# AMS_CAN.net
KiCad netlist of a schematic drawn in Altium Designer
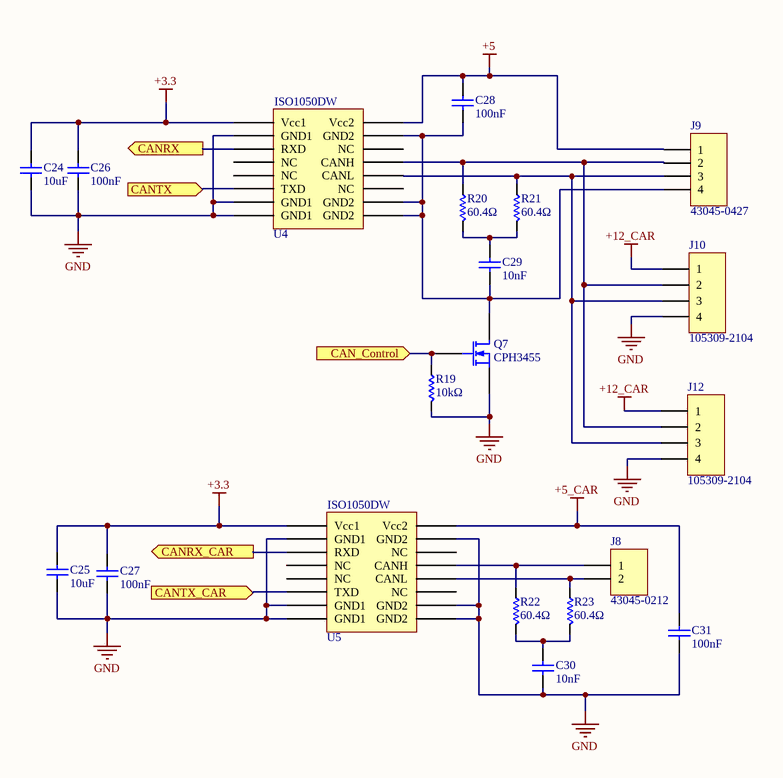
[diagram p0: AMS_CAN.SchDoc]

(export (version "E")
  (design (tool "Eeschema 10.0.6"))
  (components
    (comp (ref "C24")
      (value "10uF")
      (footprint "0805_2x1.25x1.25mm_Reflow Soldering")
      (description "WCAP-CSGP Ceramic Capacitors, 0805, X5R, 16V, 10uF")
      (fields (field (name "PART NUMBER") "885012107014") (field (name "PUBLISHER") "Wurth Elektronik"))
      (libsource (lib "Components_Library") (part "885012107014"))
    )
    (comp (ref "C25")
      (value "10uF")
      (footprint "0805_2x1.25x1.25mm_Reflow Soldering")
      (description "WCAP-CSGP Ceramic Capacitors, 0805, X5R, 16V, 10uF")
      (fields (field (name "PART NUMBER") "885012107014") (field (name "PUBLISHER") "Wurth Elektronik"))
      (libsource (lib "Components_Library") (part "885012107014"))
    )
    (comp (ref "C26")
      (value "100nF")
      (footprint "0805_2x1.25x0.8mm_Reflow Soldering")
      (description "WCAP-CSGP Ceramic Capacitors, 0805, X7R, 50V, 100nF")
      (fields (field (name "PART NUMBER") "885012207098") (field (name "PUBLISHER") "Wurth Elektronik"))
      (libsource (lib "Components_Library") (part "885012207098"))
    )
    (comp (ref "C27")
      (value "100nF")
      (footprint "0805_2x1.25x0.8mm_Reflow Soldering")
      (description "WCAP-CSGP Ceramic Capacitors, 0805, X7R, 50V, 100nF")
      (fields (field (name "PART NUMBER") "885012207098") (field (name "PUBLISHER") "Wurth Elektronik"))
      (libsource (lib "Components_Library") (part "885012207098"))
    )
    (comp (ref "C28")
      (value "100nF")
      (footprint "0805_2x1.25x0.8mm_Reflow Soldering")
      (description "WCAP-CSGP Ceramic Capacitors, 0805, X7R, 50V, 100nF")
      (fields (field (name "PART NUMBER") "885012207098") (field (name "PUBLISHER") "Wurth Elektronik"))
      (libsource (lib "Components_Library") (part "885012207098"))
    )
    (comp (ref "C29")
      (value "10nF")
      (footprint "0805_2x1.25x0.8mm_Reflow Soldering")
      (description "WCAP-CSGP Ceramic Capacitors, 0805, X7R, 50V, 10nF")
      (fields (field (name "PART NUMBER") "885012207092") (field (name "PUBLISHER") "Wurth Elektronik"))
      (libsource (lib "Components_Library") (part "885012207092"))
    )
    (comp (ref "C30")
      (value "10nF")
      (footprint "0805_2x1.25x0.8mm_Reflow Soldering")
      (description "WCAP-CSGP Ceramic Capacitors, 0805, X7R, 50V, 10nF")
      (fields (field (name "PART NUMBER") "885012207092") (field (name "PUBLISHER") "Wurth Elektronik"))
      (libsource (lib "Components_Library") (part "885012207092"))
    )
    (comp (ref "C31")
      (value "100nF")
      (footprint "0805_2x1.25x0.8mm_Reflow Soldering")
      (description "WCAP-CSGP Ceramic Capacitors, 0805, X7R, 50V, 100nF")
      (fields (field (name "PART NUMBER") "885012207098") (field (name "PUBLISHER") "Wurth Elektronik"))
      (libsource (lib "Components_Library") (part "885012207098"))
    )
    (comp (ref "J8")
      (value "43045-0212")
      (footprint "43045-0212")
      (description "Micro-Fit 3.0 Vertical Header, 3.00mm Pitch, Dual Row, 2 Circuits, Black")
      (fields (field (name "MANUFACTURER") "Molex"))
      (libsource (lib "Components_Library") (part "43045-0212"))
    )
    (comp (ref "J9")
      (value "43045-0427")
      (footprint "43045-0427")
      (description "Micro-Fit 3.0 Vertical Header, 3.00mm Pitch, Dual Row, 4 Circuits, Black")
      (fields (field (name "MANUFACTURER") "Molex"))
      (libsource (lib "Components_Library") (part "43045-0427"))
    )
    (comp (ref "J10")
      (value "105309-2104")
      (footprint "105309-2104")
      (description "Nano-Fit Vertical Header, Through Hole, 2.50mm Pitch, Single Row, 4 Circuits, Natural")
      (fields (field (name "MANUFACTURER") "Molex"))
      (libsource (lib "Components_Library") (part "105309-2104"))
    )
    (comp (ref "J12")
      (value "105309-2104")
      (footprint "105309-2104")
      (description "Nano-Fit Vertical Header, Through Hole, 2.50mm Pitch, Single Row, 4 Circuits, Natural")
      (fields (field (name "MANUFACTURER") "Molex"))
      (libsource (lib "Components_Library") (part "105309-2104"))
    )
    (comp (ref "Q7")
      (value "CPH3455")
      (footprint "CPH3455")
      (description "Power MOSFET 35V, 104mΩ, 3A, Single N-Channel")
      (fields (field (name "MANUFACTURER") "ON Semiconductors"))
      (libsource (lib "Components_Library") (part "CPH3455"))
    )
    (comp (ref "R19")
      (value "10kΩ")
      (footprint "CR0805")
      (description "Chip Resistor 0805")
      (fields (field (name "MANUFACTURER") "Bourns"))
      (libsource (lib "Components_Library") (part "CR0805-JW-103ELF"))
    )
    (comp (ref "R20")
      (value "60.4Ω")
      (footprint "CR0805")
      (description "Chip Resistor 0805")
      (fields (field (name "MANUFACTURER") "Panasonic"))
      (libsource (lib "Components_Library") (part "ERA6AEB60R4V"))
    )
    (comp (ref "R21")
      (value "60.4Ω")
      (footprint "CR0805")
      (description "Chip Resistor 0805")
      (fields (field (name "MANUFACTURER") "Panasonic"))
      (libsource (lib "Components_Library") (part "ERA6AEB60R4V"))
    )
    (comp (ref "R22")
      (value "60.4Ω")
      (footprint "CR0805")
      (description "Chip Resistor 0805")
      (fields (field (name "MANUFACTURER") "Panasonic"))
      (libsource (lib "Components_Library") (part "ERA6AEB60R4V"))
    )
    (comp (ref "R23")
      (value "60.4Ω")
      (footprint "CR0805")
      (description "Chip Resistor 0805")
      (fields (field (name "MANUFACTURER") "Panasonic"))
      (libsource (lib "Components_Library") (part "ERA6AEB60R4V"))
    )
    (comp (ref "U4")
      (value "ISO1050DW")
      (footprint "ISO1050DW")
      (description "Galvanically isolated CAN\r\ntransceiver")
      (fields (field (name "MANUFACTURER") "Texas Instruments"))
      (libsource (lib "Components_Library") (part "ISO1050DW"))
    )
    (comp (ref "U5")
      (value "ISO1050DW")
      (footprint "ISO1050DW")
      (description "Galvanically isolated CAN\r\ntransceiver")
      (fields (field (name "MANUFACTURER") "Texas Instruments"))
      (libsource (lib "Components_Library") (part "ISO1050DW"))
    )
  )
  (nets
    (net (code "1") (name "+3.3") (class "Default")
      (node (ref "C24") (pin "2") (pinfunction "2_2") (pintype "passive"))
      (node (ref "C25") (pin "2") (pinfunction "2_2") (pintype "passive"))
      (node (ref "C26") (pin "2") (pinfunction "2_2") (pintype "passive"))
      (node (ref "C27") (pin "2") (pinfunction "2_2") (pintype "passive"))
      (node (ref "U4") (pin "1") (pinfunction "Vcc1_1") (pintype "passive"))
      (node (ref "U5") (pin "1") (pinfunction "Vcc1_1") (pintype "passive"))
    )
    (net (code "2") (name "+5") (class "Default")
      (node (ref "C28") (pin "2") (pinfunction "2_2") (pintype "passive"))
      (node (ref "J9") (pin "1") (pinfunction "1_1") (pintype "passive"))
      (node (ref "U4") (pin "16") (pinfunction "Vcc2_16") (pintype "passive"))
    )
    (net (code "3") (name "+5_CAR") (class "Default")
      (node (ref "C31") (pin "2") (pinfunction "2_2") (pintype "passive"))
      (node (ref "U5") (pin "16") (pinfunction "Vcc2_16") (pintype "passive"))
    )
    (net (code "4") (name "+12_CAR") (class "Default")
      (node (ref "J10") (pin "1") (pinfunction "1_1") (pintype "passive"))
      (node (ref "J12") (pin "1") (pinfunction "1_1") (pintype "passive"))
    )
    (net (code "5") (name "/CANRX") (class "Default")
      (node (ref "U4") (pin "3") (pinfunction "RXD_3") (pintype "passive"))
    )
    (net (code "6") (name "/CANRX_CAR") (class "Default")
      (node (ref "U5") (pin "3") (pinfunction "RXD_3") (pintype "passive"))
    )
    (net (code "7") (name "/CANTX") (class "Default")
      (node (ref "U4") (pin "6") (pinfunction "TXD_6") (pintype "passive"))
    )
    (net (code "8") (name "/CANTX_CAR") (class "Default")
      (node (ref "U5") (pin "6") (pinfunction "TXD_6") (pintype "passive"))
    )
    (net (code "9") (name "/CAN_Control") (class "Default")
      (node (ref "Q7") (pin "1") (pinfunction "G_1") (pintype "passive"))
      (node (ref "R19") (pin "2") (pinfunction "2_2") (pintype "passive"))
    )
    (net (code "10") (name "GND") (class "Default")
      (node (ref "C24") (pin "1") (pinfunction "1_1") (pintype "passive"))
      (node (ref "C25") (pin "1") (pinfunction "1_1") (pintype "passive"))
      (node (ref "C26") (pin "1") (pinfunction "1_1") (pintype "passive"))
      (node (ref "C27") (pin "1") (pinfunction "1_1") (pintype "passive"))
      (node (ref "C30") (pin "1") (pinfunction "1_1") (pintype "passive"))
      (node (ref "C31") (pin "1") (pinfunction "1_1") (pintype "passive"))
      (node (ref "J10") (pin "4") (pinfunction "4_4") (pintype "passive"))
      (node (ref "J12") (pin "4") (pinfunction "4_4") (pintype "passive"))
      (node (ref "Q7") (pin "2") (pinfunction "S_2") (pintype "passive"))
      (node (ref "R19") (pin "1") (pinfunction "1_1") (pintype "passive"))
      (node (ref "U4") (pin "2") (pinfunction "GND1_2") (pintype "passive"))
      (node (ref "U4") (pin "7") (pinfunction "GND1_7") (pintype "passive"))
      (node (ref "U4") (pin "8") (pinfunction "GND1_8") (pintype "passive"))
      (node (ref "U5") (pin "10") (pinfunction "GND2_10") (pintype "passive"))
      (node (ref "U5") (pin "15") (pinfunction "GND2_15") (pintype "passive"))
      (node (ref "U5") (pin "2") (pinfunction "GND1_2") (pintype "passive"))
      (node (ref "U5") (pin "7") (pinfunction "GND1_7") (pintype "passive"))
      (node (ref "U5") (pin "8") (pinfunction "GND1_8") (pintype "passive"))
      (node (ref "U5") (pin "9") (pinfunction "GND2_9") (pintype "passive"))
    )
    (net (code "11") (name "Net-(C29-Pad2)") (class "Default")
      (node (ref "C29") (pin "2") (pinfunction "2_2") (pintype "passive"))
      (node (ref "R20") (pin "1") (pinfunction "1_1") (pintype "passive"))
      (node (ref "R21") (pin "1") (pinfunction "1_1") (pintype "passive"))
    )
    (net (code "12") (name "Net-(C30-Pad2)") (class "Default")
      (node (ref "C30") (pin "2") (pinfunction "2_2") (pintype "passive"))
      (node (ref "R22") (pin "1") (pinfunction "1_1") (pintype "passive"))
      (node (ref "R23") (pin "1") (pinfunction "1_1") (pintype "passive"))
    )
    (net (code "13") (name "Net-(Q7-D)") (class "Default")
      (node (ref "C28") (pin "1") (pinfunction "1_1") (pintype "passive"))
      (node (ref "C29") (pin "1") (pinfunction "1_1") (pintype "passive"))
      (node (ref "J9") (pin "4") (pinfunction "4_4") (pintype "passive"))
      (node (ref "Q7") (pin "3") (pinfunction "D_3") (pintype "passive"))
      (node (ref "U4") (pin "10") (pinfunction "GND2_10") (pintype "passive"))
      (node (ref "U4") (pin "15") (pinfunction "GND2_15") (pintype "passive"))
      (node (ref "U4") (pin "9") (pinfunction "GND2_9") (pintype "passive"))
    )
    (net (code "14") (name "Net-(U4-CANH)") (class "Default")
      (node (ref "J10") (pin "2") (pinfunction "2_2") (pintype "passive"))
      (node (ref "J12") (pin "2") (pinfunction "2_2") (pintype "passive"))
      (node (ref "J9") (pin "2") (pinfunction "2_2") (pintype "passive"))
      (node (ref "R20") (pin "2") (pinfunction "2_2") (pintype "passive"))
      (node (ref "U4") (pin "13") (pinfunction "CANH_13") (pintype "passive"))
    )
    (net (code "15") (name "Net-(U4-CANL)") (class "Default")
      (node (ref "J10") (pin "3") (pinfunction "3_3") (pintype "passive"))
      (node (ref "J12") (pin "3") (pinfunction "3_3") (pintype "passive"))
      (node (ref "J9") (pin "3") (pinfunction "3_3") (pintype "passive"))
      (node (ref "R21") (pin "2") (pinfunction "2_2") (pintype "passive"))
      (node (ref "U4") (pin "12") (pinfunction "CANL_12") (pintype "passive"))
    )
    (net (code "16") (name "Net-(U5-CANH)") (class "Default")
      (node (ref "J8") (pin "1") (pinfunction "1_1") (pintype "passive"))
      (node (ref "R22") (pin "2") (pinfunction "2_2") (pintype "passive"))
      (node (ref "U5") (pin "13") (pinfunction "CANH_13") (pintype "passive"))
    )
    (net (code "17") (name "Net-(U5-CANL)") (class "Default")
      (node (ref "J8") (pin "2") (pinfunction "2_2") (pintype "passive"))
      (node (ref "R23") (pin "2") (pinfunction "2_2") (pintype "passive"))
      (node (ref "U5") (pin "12") (pinfunction "CANL_12") (pintype "passive"))
    )
    (net (code "18") (name "unconnected-(U4-NC-Pad4)") (class "Default")
      (node (ref "U4") (pin "4") (pinfunction "NC_4") (pintype "passive"))
    )
    (net (code "19") (name "unconnected-(U4-NC-Pad5)") (class "Default")
      (node (ref "U4") (pin "5") (pinfunction "NC_5") (pintype "passive"))
    )
    (net (code "20") (name "unconnected-(U4-NC-Pad11)") (class "Default")
      (node (ref "U4") (pin "11") (pinfunction "NC_11") (pintype "passive"))
    )
    (net (code "21") (name "unconnected-(U4-NC-Pad14)") (class "Default")
      (node (ref "U4") (pin "14") (pinfunction "NC_14") (pintype "passive"))
    )
    (net (code "22") (name "unconnected-(U5-NC-Pad4)") (class "Default")
      (node (ref "U5") (pin "4") (pinfunction "NC_4") (pintype "passive"))
    )
    (net (code "23") (name "unconnected-(U5-NC-Pad5)") (class "Default")
      (node (ref "U5") (pin "5") (pinfunction "NC_5") (pintype "passive"))
    )
    (net (code "24") (name "unconnected-(U5-NC-Pad11)") (class "Default")
      (node (ref "U5") (pin "11") (pinfunction "NC_11") (pintype "passive"))
    )
    (net (code "25") (name "unconnected-(U5-NC-Pad14)") (class "Default")
      (node (ref "U5") (pin "14") (pinfunction "NC_14") (pintype "passive"))
    )
  )
)
